# 250100020129x-HW-V2_4.net
KiCad netlist of a schematic drawn in EAGLE
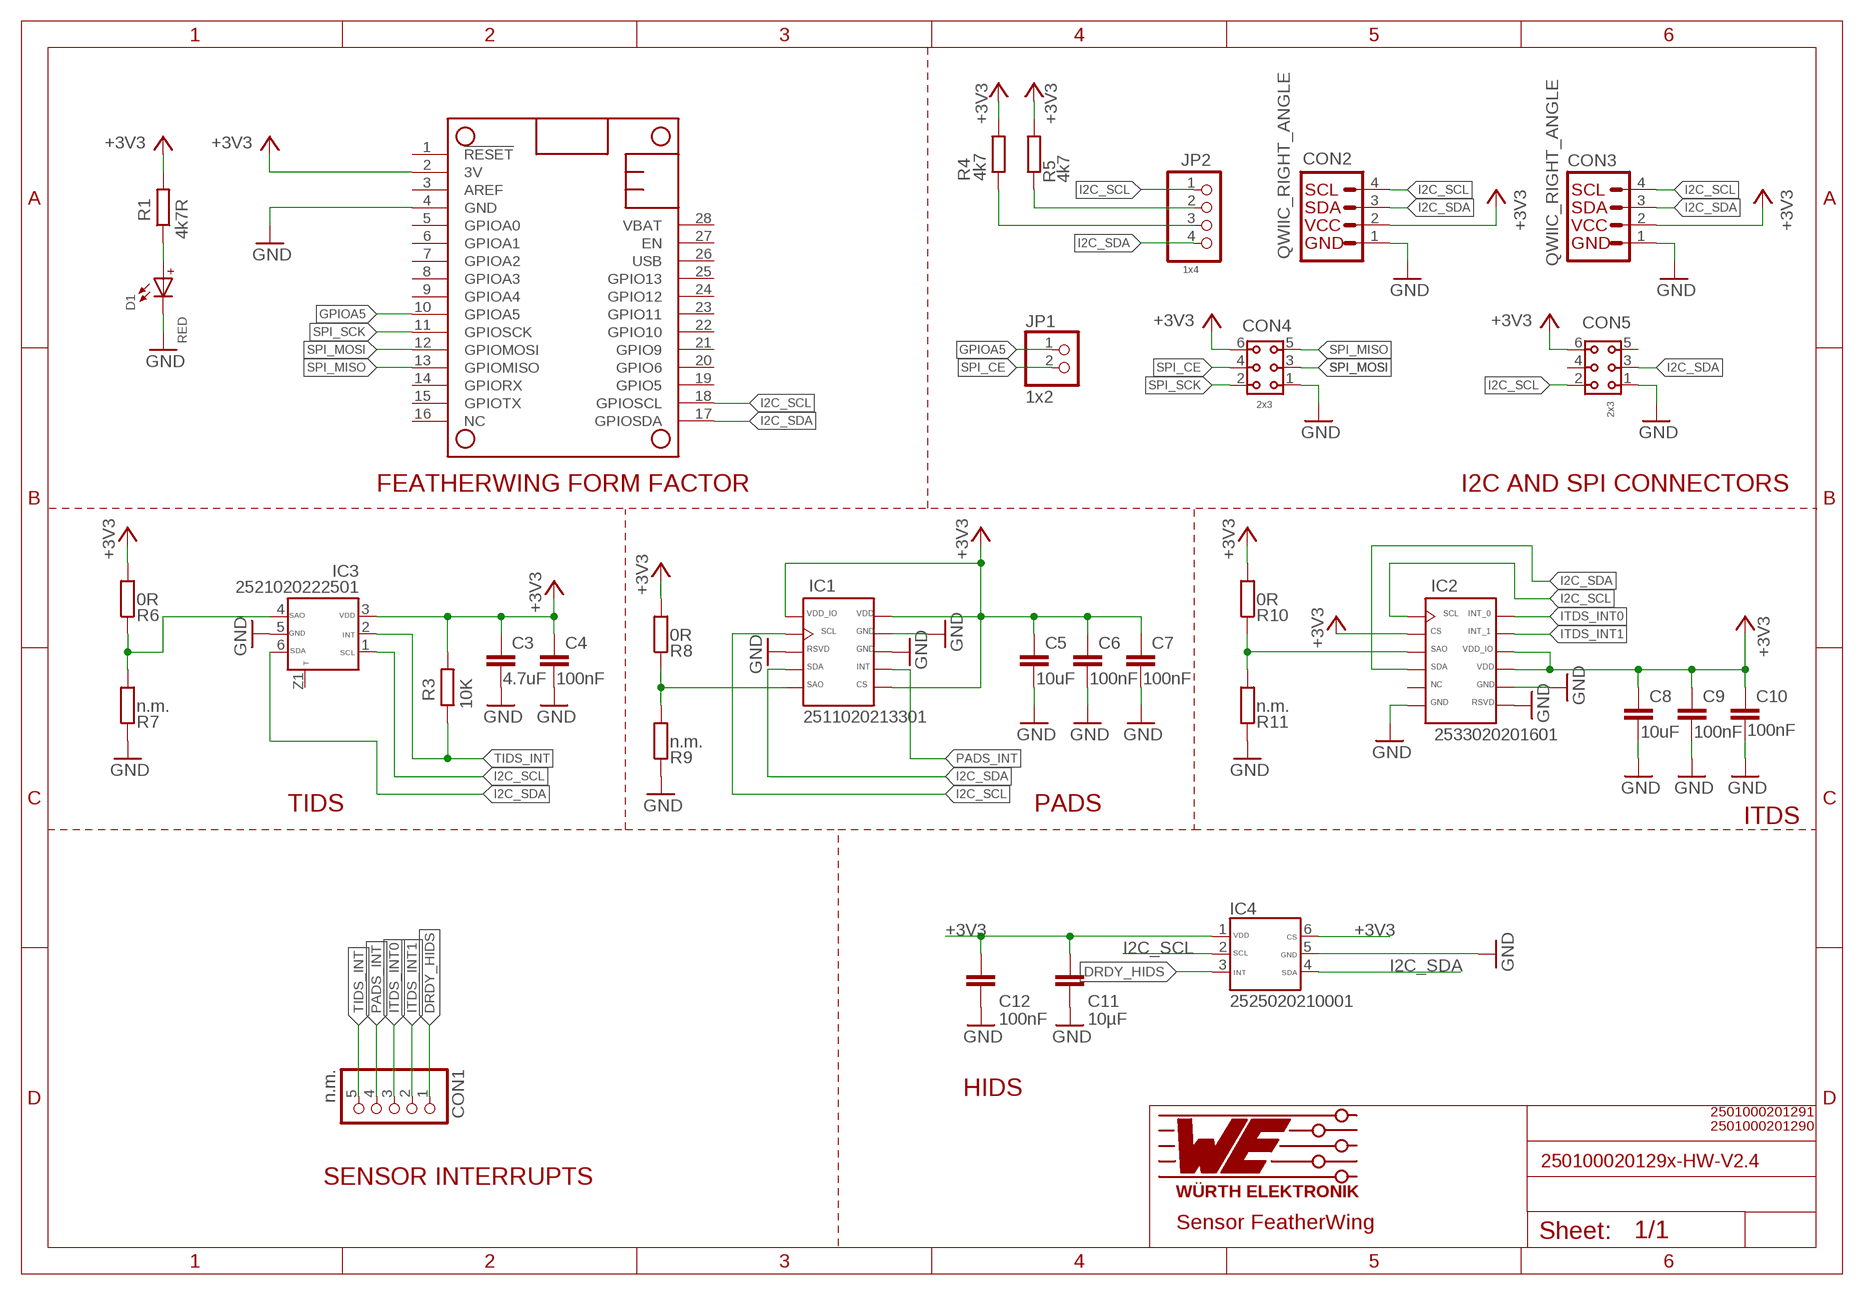
[diagram p0: schematic, sheet 1]

(export (version "E")
  (design (tool "Eeschema 10.0.6"))
  (components
    (comp (ref "C3")
      (value "4.7uF")
      (footprint "eagle-import:C0402_IPC")
      (fields (field (name "MANUFACTURER") "Würth Elektronik"))
      (libsource (lib "eagle-import") (part "C0402_IPC4.7UF"))
    )
    (comp (ref "C4")
      (value "100nF")
      (footprint "eagle-import:C0402_IPC")
      (fields (field (name "MANUFACTURER") "Würth Elektronik"))
      (libsource (lib "eagle-import") (part "C0402_IPC100NF"))
    )
    (comp (ref "C5")
      (value "10uF")
      (footprint "eagle-import:C0402_IPC")
      (fields (field (name "MANUFACTURER") "Würth Elektronik"))
      (libsource (lib "eagle-import") (part "C0402_IPC10UF"))
    )
    (comp (ref "C6")
      (value "100nF")
      (footprint "eagle-import:C0402_IPC")
      (fields (field (name "MANUFACTURER") "Würth Elektronik"))
      (libsource (lib "eagle-import") (part "C0402_IPC100NF"))
    )
    (comp (ref "C7")
      (value "100nF")
      (footprint "eagle-import:C0402_IPC")
      (fields (field (name "MANUFACTURER") "Würth Elektronik"))
      (libsource (lib "eagle-import") (part "C0402_IPC100NF"))
    )
    (comp (ref "C8")
      (value "10uF")
      (footprint "eagle-import:C0402_IPC")
      (fields (field (name "MANUFACTURER") "Würth Elektronik"))
      (libsource (lib "eagle-import") (part "C0402_IPC10UF"))
    )
    (comp (ref "C9")
      (value "100nF")
      (footprint "eagle-import:C0402_IPC")
      (fields (field (name "MANUFACTURER") "Würth Elektronik"))
      (libsource (lib "eagle-import") (part "C0402_IPC100NF"))
    )
    (comp (ref "C10")
      (value "100nF")
      (footprint "eagle-import:C0402_IPC")
      (fields (field (name "MANUFACTURER") "Würth Elektronik"))
      (libsource (lib "eagle-import") (part "C0402_IPC100NF"))
    )
    (comp (ref "C11")
      (value "10µF")
      (footprint "eagle-import:C0402_IPC")
      (fields (field (name "MANUFACTURER") "Würth Elektronik"))
      (libsource (lib "eagle-import") (part "C0402_IPC10UF"))
    )
    (comp (ref "C12")
      (value "100nF")
      (footprint "eagle-import:C0402_IPC")
      (fields (field (name "MANUFACTURER") "Würth Elektronik"))
      (libsource (lib "eagle-import") (part "C0402_IPC100NF"))
    )
    (comp (ref "CON1")
      (value "n.m.")
      (footprint "eagle-import:1X05_R")
      (fields (field (name "MANUFACTURER") "Würth Elektronik"))
      (libsource (lib "eagle-import") (part "PINHD-1X5/R"))
    )
    (comp (ref "CON2")
      (value "QWIIC_RIGHT_ANGLE")
      (footprint "eagle-import:JST04_1MM_RA")
      (fields (field (name "MANUFACTURER") "JST"))
      (libsource (lib "eagle-import") (part "QWIIC_CONNECTORJS-1MM"))
    )
    (comp (ref "CON3")
      (value "QWIIC_RIGHT_ANGLE")
      (footprint "eagle-import:JST04_1MM_RA")
      (fields (field (name "MANUFACTURER") "JST"))
      (libsource (lib "eagle-import") (part "QWIIC_CONNECTORJS-1MM"))
    )
    (comp (ref "CON4")
      (value "2x3")
      (footprint "eagle-import:613006243121")
      (fields (field (name "MANUFACTURER") "Würth Elektronik") (field (name "COMMENT") "Stick out of PCB"))
      (libsource (lib "eagle-import") (part "6130XX243121_613006243121"))
    )
    (comp (ref "CON5")
      (value "2x3")
      (footprint "eagle-import:613006243121")
      (fields (field (name "MANUFACTURER") "Würth Elektronik") (field (name "COMMENT") "Stick out of PCB"))
      (libsource (lib "eagle-import") (part "6130XX243121_613006243121"))
    )
    (comp (ref "D1")
      (value "RED")
      (footprint "eagle-import:WL-SMSW_1204_A")
      (fields (field (name "MANUFACTURER") "Würth Elektronik"))
      (libsource (lib "eagle-import") (part "WL-SMSW_1204_155124VS73200"))
    )
    (comp (ref "IC1")
      (value "2511020213301")
      (footprint "eagle-import:WSEN-PADS_2511020213301")
      (fields (field (name "MANUFACTURER") "Würth Elektronik"))
      (libsource (lib "eagle-import") (part "WSEN-PADS_2511020213301"))
    )
    (comp (ref "IC2")
      (value "2533020201601")
      (footprint "eagle-import:WSEN-ITDS_2533020201601")
      (fields (field (name "MANUFACTURER") "Würth Elektronik"))
      (libsource (lib "eagle-import") (part "WSEN-ITDS_2533020201601"))
    )
    (comp (ref "IC3")
      (value "2521020222501")
      (footprint "eagle-import:WSEN-TIDS_2521020222501")
      (fields (field (name "MANUFACTURER") "Würth Elektronik"))
      (libsource (lib "eagle-import") (part "WSEN-TIDS_2521020222501"))
    )
    (comp (ref "IC4")
      (value "2525020210001")
      (footprint "eagle-import:WSEN-HIDS_2525020210001")
      (fields (field (name "MANUFACTURER") "Würth Elektronik") (field (name "HEIGHT") "1.0mm"))
      (libsource (lib "eagle-import") (part "WSEN-HIDS_2525020210001"))
    )
    (comp (ref "JP1")
      (value "1x2")
      (footprint "eagle-import:1X02_R")
      (fields (field (name "MANUFACTURER") "Würth Elektronik"))
      (libsource (lib "eagle-import") (part "PINHD-1X2/R"))
    )
    (comp (ref "JP2")
      (value "1x4")
      (footprint "eagle-import:1X04_R")
      (fields (field (name "COMMENT") "2xJumper, 1-2, 3-4") (field (name "MANUFACTURER") "Würth Elektronik"))
      (libsource (lib "eagle-import") (part "PINHD-1X4/R"))
    )
    (comp (ref "MS1")
      (value "FEATHERWING")
      (footprint "eagle-import:FEATHERWING")
      (fields
        (field (name "COMMENT") "header: 1 x 12 & 1 x 16, stackup, pins clean")
        (field (name "MANUFACTURER") "Adafruit")
      )
      (libsource (lib "eagle-import") (part "FEATHERWING"))
    )
    (comp (ref "R1")
      (value "4k7R")
      (footprint "eagle-import:R0402_IPC")
      (fields (field (name "MANUFACTURER") "Yageo"))
      (libsource (lib "eagle-import") (part "R0402_IPC4K7"))
    )
    (comp (ref "R3")
      (value "10K")
      (footprint "eagle-import:R0402_IPC")
      (fields (field (name "MANUFACTURER") "Yageo"))
      (libsource (lib "eagle-import") (part "R0402_IPC10KR"))
    )
    (comp (ref "R4")
      (value "4k7")
      (footprint "eagle-import:R0402_IPC")
      (fields (field (name "MANUFACTURER") "Yageo"))
      (libsource (lib "eagle-import") (part "R0402_IPC4K7"))
    )
    (comp (ref "R5")
      (value "4k7")
      (footprint "eagle-import:R0402_IPC")
      (fields (field (name "MANUFACTURER") "Yageo"))
      (libsource (lib "eagle-import") (part "R0402_IPC4K7"))
    )
    (comp (ref "R6")
      (value "0R")
      (footprint "eagle-import:R0402_IPC")
      (fields (field (name "MANUFACTURER") "Yageo"))
      (libsource (lib "eagle-import") (part "R0402_IPC0R"))
    )
    (comp (ref "R7")
      (value "n.m.")
      (footprint "eagle-import:R0402_IPC")
      (fields (field (name "MANUFACTURER") "Yageo"))
      (libsource (lib "eagle-import") (part "R0402_IPC"))
    )
    (comp (ref "R8")
      (value "0R")
      (footprint "eagle-import:R0402_IPC")
      (fields (field (name "MANUFACTURER") "Yageo"))
      (libsource (lib "eagle-import") (part "R0402_IPC0R"))
    )
    (comp (ref "R9")
      (value "n.m.")
      (footprint "eagle-import:R0402_IPC")
      (fields (field (name "MANUFACTURER") "Yageo"))
      (libsource (lib "eagle-import") (part "R0402_IPC"))
    )
    (comp (ref "R10")
      (value "0R")
      (footprint "eagle-import:R0402_IPC")
      (fields (field (name "MANUFACTURER") "Yageo"))
      (libsource (lib "eagle-import") (part "R0402_IPC0R"))
    )
    (comp (ref "R11")
      (value "n.m.")
      (footprint "eagle-import:R0402_IPC")
      (fields (field (name "MANUFACTURER") "Yageo"))
      (libsource (lib "eagle-import") (part "R0402_IPC"))
    )
  )
  (nets
    (net (code "1") (name "+3V3") (class "Default")
      (node (ref "C10") (pin "1") (pinfunction "1_1") (pintype "passive"))
      (node (ref "C11") (pin "2") (pinfunction "2_2") (pintype "passive"))
      (node (ref "C12") (pin "2") (pinfunction "2_2") (pintype "passive"))
      (node (ref "C3") (pin "1") (pinfunction "1_1") (pintype "passive"))
      (node (ref "C4") (pin "1") (pinfunction "1_1") (pintype "passive"))
      (node (ref "C5") (pin "1") (pinfunction "1_1") (pintype "passive"))
      (node (ref "C6") (pin "1") (pinfunction "1_1") (pintype "passive"))
      (node (ref "C7") (pin "1") (pinfunction "1_1") (pintype "passive"))
      (node (ref "C8") (pin "1") (pinfunction "1_1") (pintype "passive"))
      (node (ref "C9") (pin "1") (pinfunction "1_1") (pintype "passive"))
      (node (ref "CON2") (pin "2") (pinfunction "2_2") (pintype "power_in"))
      (node (ref "CON3") (pin "2") (pinfunction "2_2") (pintype "power_in"))
      (node (ref "CON4") (pin "6") (pinfunction "6_6") (pintype "passive"))
      (node (ref "CON5") (pin "6") (pinfunction "6_6") (pintype "passive"))
      (node (ref "IC1") (pin "1") (pinfunction "VDD_IO_1") (pintype "power_in"))
      (node (ref "IC1") (pin "10") (pinfunction "VDD_10") (pintype "power_in"))
      (node (ref "IC1") (pin "6") (pinfunction "CS_6") (pintype "input"))
      (node (ref "IC2") (pin "10") (pinfunction "VDD_IO_10") (pintype "power_in"))
      (node (ref "IC2") (pin "2") (pinfunction "CS_2") (pintype "input"))
      (node (ref "IC2") (pin "9") (pinfunction "VDD_9") (pintype "power_in"))
      (node (ref "IC3") (pin "3") (pinfunction "VDD_3") (pintype "power_in"))
      (node (ref "IC4") (pin "1") (pinfunction "VDD_1") (pintype "power_in"))
      (node (ref "IC4") (pin "6") (pinfunction "CS_6") (pintype "passive"))
      (node (ref "MS1") (pin "2") (pinfunction "3V_2") (pintype "power_in"))
      (node (ref "R1") (pin "2") (pinfunction "2_2") (pintype "passive"))
      (node (ref "R10") (pin "2") (pinfunction "2_2") (pintype "passive"))
      (node (ref "R3") (pin "2") (pinfunction "2_2") (pintype "passive"))
      (node (ref "R4") (pin "2") (pinfunction "2_2") (pintype "passive"))
      (node (ref "R5") (pin "2") (pinfunction "2_2") (pintype "passive"))
      (node (ref "R6") (pin "2") (pinfunction "2_2") (pintype "passive"))
      (node (ref "R8") (pin "2") (pinfunction "2_2") (pintype "passive"))
    )
    (net (code "2") (name "/USB") (class "Default")
      (node (ref "MS1") (pin "26") (pinfunction "USB_26") (pintype "power_in"))
    )
    (net (code "3") (name "/VBAT") (class "Default")
      (node (ref "MS1") (pin "28") (pinfunction "VBAT_28") (pintype "power_in"))
    )
    (net (code "4") (name "DRDY_HIDS") (class "Default")
      (node (ref "CON1") (pin "1") (pinfunction "1_1") (pintype "passive"))
      (node (ref "IC4") (pin "3") (pinfunction "INT_3") (pintype "output"))
    )
    (net (code "5") (name "GND") (class "Default")
      (node (ref "C10") (pin "2") (pinfunction "2_2") (pintype "passive"))
      (node (ref "C11") (pin "1") (pinfunction "1_1") (pintype "passive"))
      (node (ref "C12") (pin "1") (pinfunction "1_1") (pintype "passive"))
      (node (ref "C3") (pin "2") (pinfunction "2_2") (pintype "passive"))
      (node (ref "C4") (pin "2") (pinfunction "2_2") (pintype "passive"))
      (node (ref "C5") (pin "2") (pinfunction "2_2") (pintype "passive"))
      (node (ref "C6") (pin "2") (pinfunction "2_2") (pintype "passive"))
      (node (ref "C7") (pin "2") (pinfunction "2_2") (pintype "passive"))
      (node (ref "C8") (pin "2") (pinfunction "2_2") (pintype "passive"))
      (node (ref "C9") (pin "2") (pinfunction "2_2") (pintype "passive"))
      (node (ref "CON2") (pin "1") (pinfunction "1_1") (pintype "power_in"))
      (node (ref "CON3") (pin "1") (pinfunction "1_1") (pintype "power_in"))
      (node (ref "CON4") (pin "1") (pinfunction "1_1") (pintype "passive"))
      (node (ref "CON5") (pin "1") (pinfunction "1_1") (pintype "passive"))
      (node (ref "D1") (pin "1") (pinfunction "-_1") (pintype "passive"))
      (node (ref "IC1") (pin "3") (pinfunction "RSVD_3") (pintype "bidirectional"))
      (node (ref "IC1") (pin "8") (pinfunction "GND_8") (pintype "power_in"))
      (node (ref "IC1") (pin "9") (pinfunction "GND_9") (pintype "power_in"))
      (node (ref "IC2") (pin "6") (pinfunction "GND_6") (pintype "power_in"))
      (node (ref "IC2") (pin "7") (pinfunction "RSVD_7") (pintype "bidirectional"))
      (node (ref "IC2") (pin "8") (pinfunction "GND_8") (pintype "power_in"))
      (node (ref "IC3") (pin "5") (pinfunction "GND_5") (pintype "power_in"))
      (node (ref "IC4") (pin "5") (pinfunction "GND_5") (pintype "power_in"))
      (node (ref "MS1") (pin "4") (pinfunction "GND_4") (pintype "power_in"))
      (node (ref "R11") (pin "1") (pinfunction "1_1") (pintype "passive"))
      (node (ref "R7") (pin "1") (pinfunction "1_1") (pintype "passive"))
      (node (ref "R9") (pin "1") (pinfunction "1_1") (pintype "passive"))
    )
    (net (code "6") (name "GPIOA5") (class "Default")
      (node (ref "JP1") (pin "1") (pinfunction "1_1") (pintype "passive"))
      (node (ref "MS1") (pin "10") (pinfunction "GPIOA5_10") (pintype "bidirectional"))
    )
    (net (code "7") (name "I2C_SCL") (class "Default")
      (node (ref "CON2") (pin "4") (pinfunction "4_4") (pintype "passive"))
      (node (ref "CON3") (pin "4") (pinfunction "4_4") (pintype "passive"))
      (node (ref "CON5") (pin "2") (pinfunction "2_2") (pintype "passive"))
      (node (ref "IC1") (pin "2") (pinfunction "SCL_2") (pintype "input"))
      (node (ref "IC2") (pin "1") (pinfunction "SCL_1") (pintype "input"))
      (node (ref "IC3") (pin "1") (pinfunction "SCL_1") (pintype "bidirectional"))
      (node (ref "IC4") (pin "2") (pinfunction "SCL_2") (pintype "bidirectional"))
      (node (ref "JP2") (pin "1") (pinfunction "1_1") (pintype "passive"))
      (node (ref "MS1") (pin "18") (pinfunction "GPIOSCL_18") (pintype "bidirectional"))
    )
    (net (code "8") (name "I2C_SDA") (class "Default")
      (node (ref "CON2") (pin "3") (pinfunction "3_3") (pintype "passive"))
      (node (ref "CON3") (pin "3") (pinfunction "3_3") (pintype "passive"))
      (node (ref "CON5") (pin "3") (pinfunction "3_3") (pintype "passive"))
      (node (ref "IC1") (pin "4") (pinfunction "SDA_4") (pintype "bidirectional"))
      (node (ref "IC2") (pin "4") (pinfunction "SDA_4") (pintype "bidirectional"))
      (node (ref "IC3") (pin "6") (pinfunction "SDA_6") (pintype "bidirectional"))
      (node (ref "IC4") (pin "4") (pinfunction "SDA_4") (pintype "bidirectional"))
      (node (ref "JP2") (pin "4") (pinfunction "4_4") (pintype "passive"))
      (node (ref "MS1") (pin "17") (pinfunction "GPIOSDA_17") (pintype "bidirectional"))
    )
    (net (code "9") (name "ITDS_INT0") (class "Default")
      (node (ref "CON1") (pin "3") (pinfunction "3_3") (pintype "passive"))
      (node (ref "IC2") (pin "12") (pinfunction "INT_0_12") (pintype "output"))
    )
    (net (code "10") (name "ITDS_INT1") (class "Default")
      (node (ref "CON1") (pin "2") (pinfunction "2_2") (pintype "passive"))
      (node (ref "IC2") (pin "11") (pinfunction "INT_1_11") (pintype "bidirectional"))
    )
    (net (code "11") (name "Net-(D1-+)") (class "Default")
      (node (ref "D1") (pin "2") (pinfunction "+_2") (pintype "passive"))
      (node (ref "R1") (pin "1") (pinfunction "1_1") (pintype "passive"))
    )
    (net (code "12") (name "Net-(IC1-SAO)") (class "Default")
      (node (ref "IC1") (pin "5") (pinfunction "SAO_5") (pintype "bidirectional"))
      (node (ref "R8") (pin "1") (pinfunction "1_1") (pintype "passive"))
      (node (ref "R9") (pin "2") (pinfunction "2_2") (pintype "passive"))
    )
    (net (code "13") (name "Net-(IC2-SAO)") (class "Default")
      (node (ref "IC2") (pin "3") (pinfunction "SAO_3") (pintype "bidirectional"))
      (node (ref "R10") (pin "1") (pinfunction "1_1") (pintype "passive"))
      (node (ref "R11") (pin "2") (pinfunction "2_2") (pintype "passive"))
    )
    (net (code "14") (name "Net-(IC3-SAO)") (class "Default")
      (node (ref "IC3") (pin "4") (pinfunction "SAO_4") (pintype "bidirectional"))
      (node (ref "R6") (pin "1") (pinfunction "1_1") (pintype "passive"))
      (node (ref "R7") (pin "2") (pinfunction "2_2") (pintype "passive"))
    )
    (net (code "15") (name "Net-(JP2-Pad2)") (class "Default")
      (node (ref "JP2") (pin "2") (pinfunction "2_2") (pintype "passive"))
      (node (ref "R5") (pin "1") (pinfunction "1_1") (pintype "passive"))
    )
    (net (code "16") (name "Net-(JP2-Pad3)") (class "Default")
      (node (ref "JP2") (pin "3") (pinfunction "3_3") (pintype "passive"))
      (node (ref "R4") (pin "1") (pinfunction "1_1") (pintype "passive"))
    )
    (net (code "17") (name "PADS_INT") (class "Default")
      (node (ref "CON1") (pin "4") (pinfunction "4_4") (pintype "passive"))
      (node (ref "IC1") (pin "7") (pinfunction "INT_7") (pintype "output"))
    )
    (net (code "18") (name "SPI_CE") (class "Default")
      (node (ref "CON4") (pin "4") (pinfunction "4_4") (pintype "passive"))
      (node (ref "JP1") (pin "2") (pinfunction "2_2") (pintype "passive"))
    )
    (net (code "19") (name "SPI_MISO") (class "Default")
      (node (ref "CON4") (pin "5") (pinfunction "5_5") (pintype "passive"))
      (node (ref "MS1") (pin "13") (pinfunction "GPIOMISO_13") (pintype "bidirectional"))
    )
    (net (code "20") (name "SPI_MOSI") (class "Default")
      (node (ref "CON4") (pin "3") (pinfunction "3_3") (pintype "passive"))
      (node (ref "MS1") (pin "12") (pinfunction "GPIOMOSI_12") (pintype "bidirectional"))
    )
    (net (code "21") (name "SPI_SCK") (class "Default")
      (node (ref "CON4") (pin "2") (pinfunction "2_2") (pintype "passive"))
      (node (ref "MS1") (pin "11") (pinfunction "GPIOSCK_11") (pintype "bidirectional"))
    )
    (net (code "22") (name "TIDS_INT") (class "Default")
      (node (ref "CON1") (pin "5") (pinfunction "5_5") (pintype "passive"))
      (node (ref "IC3") (pin "2") (pinfunction "INT_2") (pintype "bidirectional"))
      (node (ref "R3") (pin "1") (pinfunction "1_1") (pintype "passive"))
    )
    (net (code "23") (name "unconnected-(CON5-Pad4)") (class "Default")
      (node (ref "CON5") (pin "4") (pinfunction "4_4") (pintype "passive"))
    )
    (net (code "24") (name "unconnected-(CON5-Pad5)") (class "Default")
      (node (ref "CON5") (pin "5") (pinfunction "5_5") (pintype "passive"))
    )
    (net (code "25") (name "unconnected-(IC2-NC-Pad5)") (class "Default")
      (node (ref "IC2") (pin "5") (pinfunction "NC_5") (pintype "no_connect"))
    )
    (net (code "26") (name "unconnected-(IC3-P$1-PadZ1)") (class "Default")
      (node (ref "IC3") (pin "Z1") (pinfunction "P$1_Z1") (pintype "bidirectional"))
    )
    (net (code "27") (name "unconnected-(MS1-AREF-Pad3)") (class "Default")
      (node (ref "MS1") (pin "3") (pinfunction "AREF_3") (pintype "passive"))
    )
    (net (code "28") (name "unconnected-(MS1-EN-Pad27)") (class "Default")
      (node (ref "MS1") (pin "27") (pinfunction "EN_27") (pintype "passive"))
    )
    (net (code "29") (name "unconnected-(MS1-GPIO5-Pad19)") (class "Default")
      (node (ref "MS1") (pin "19") (pinfunction "GPIO5_19") (pintype "bidirectional"))
    )
    (net (code "30") (name "unconnected-(MS1-GPIO6-Pad20)") (class "Default")
      (node (ref "MS1") (pin "20") (pinfunction "GPIO6_20") (pintype "bidirectional"))
    )
    (net (code "31") (name "unconnected-(MS1-GPIO9-Pad21)") (class "Default")
      (node (ref "MS1") (pin "21") (pinfunction "GPIO9_21") (pintype "bidirectional"))
    )
    (net (code "32") (name "unconnected-(MS1-GPIO10-Pad22)") (class "Default")
      (node (ref "MS1") (pin "22") (pinfunction "GPIO10_22") (pintype "bidirectional"))
    )
    (net (code "33") (name "unconnected-(MS1-GPIO11-Pad23)") (class "Default")
      (node (ref "MS1") (pin "23") (pinfunction "GPIO11_23") (pintype "bidirectional"))
    )
    (net (code "34") (name "unconnected-(MS1-GPIO12-Pad24)") (class "Default")
      (node (ref "MS1") (pin "24") (pinfunction "GPIO12_24") (pintype "bidirectional"))
    )
    (net (code "35") (name "unconnected-(MS1-GPIO13-Pad25)") (class "Default")
      (node (ref "MS1") (pin "25") (pinfunction "GPIO13_25") (pintype "bidirectional"))
    )
    (net (code "36") (name "unconnected-(MS1-GPIOA0-Pad5)") (class "Default")
      (node (ref "MS1") (pin "5") (pinfunction "GPIOA0_5") (pintype "bidirectional"))
    )
    (net (code "37") (name "unconnected-(MS1-GPIOA1-Pad6)") (class "Default")
      (node (ref "MS1") (pin "6") (pinfunction "GPIOA1_6") (pintype "bidirectional"))
    )
    (net (code "38") (name "unconnected-(MS1-GPIOA2-Pad7)") (class "Default")
      (node (ref "MS1") (pin "7") (pinfunction "GPIOA2_7") (pintype "bidirectional"))
    )
    (net (code "39") (name "unconnected-(MS1-GPIOA3-Pad8)") (class "Default")
      (node (ref "MS1") (pin "8") (pinfunction "GPIOA3_8") (pintype "bidirectional"))
    )
    (net (code "40") (name "unconnected-(MS1-GPIOA4-Pad9)") (class "Default")
      (node (ref "MS1") (pin "9") (pinfunction "GPIOA4_9") (pintype "bidirectional"))
    )
    (net (code "41") (name "unconnected-(MS1-GPIORX-Pad14)") (class "Default")
      (node (ref "MS1") (pin "14") (pinfunction "GPIORX_14") (pintype "bidirectional"))
    )
    (net (code "42") (name "unconnected-(MS1-GPIOTX-Pad15)") (class "Default")
      (node (ref "MS1") (pin "15") (pinfunction "GPIOTX_15") (pintype "bidirectional"))
    )
    (net (code "43") (name "unconnected-(MS1-NC-Pad16)") (class "Default")
      (node (ref "MS1") (pin "16") (pinfunction "NC_16") (pintype "passive"))
    )
    (net (code "44") (name "unconnected-(MS1-~{RESET}-Pad1)") (class "Default")
      (node (ref "MS1") (pin "1") (pinfunction "~{RESET}_1") (pintype "input"))
    )
  )
)
